# DynStudent.net
KiCad netlist of a schematic drawn in Altium Designer
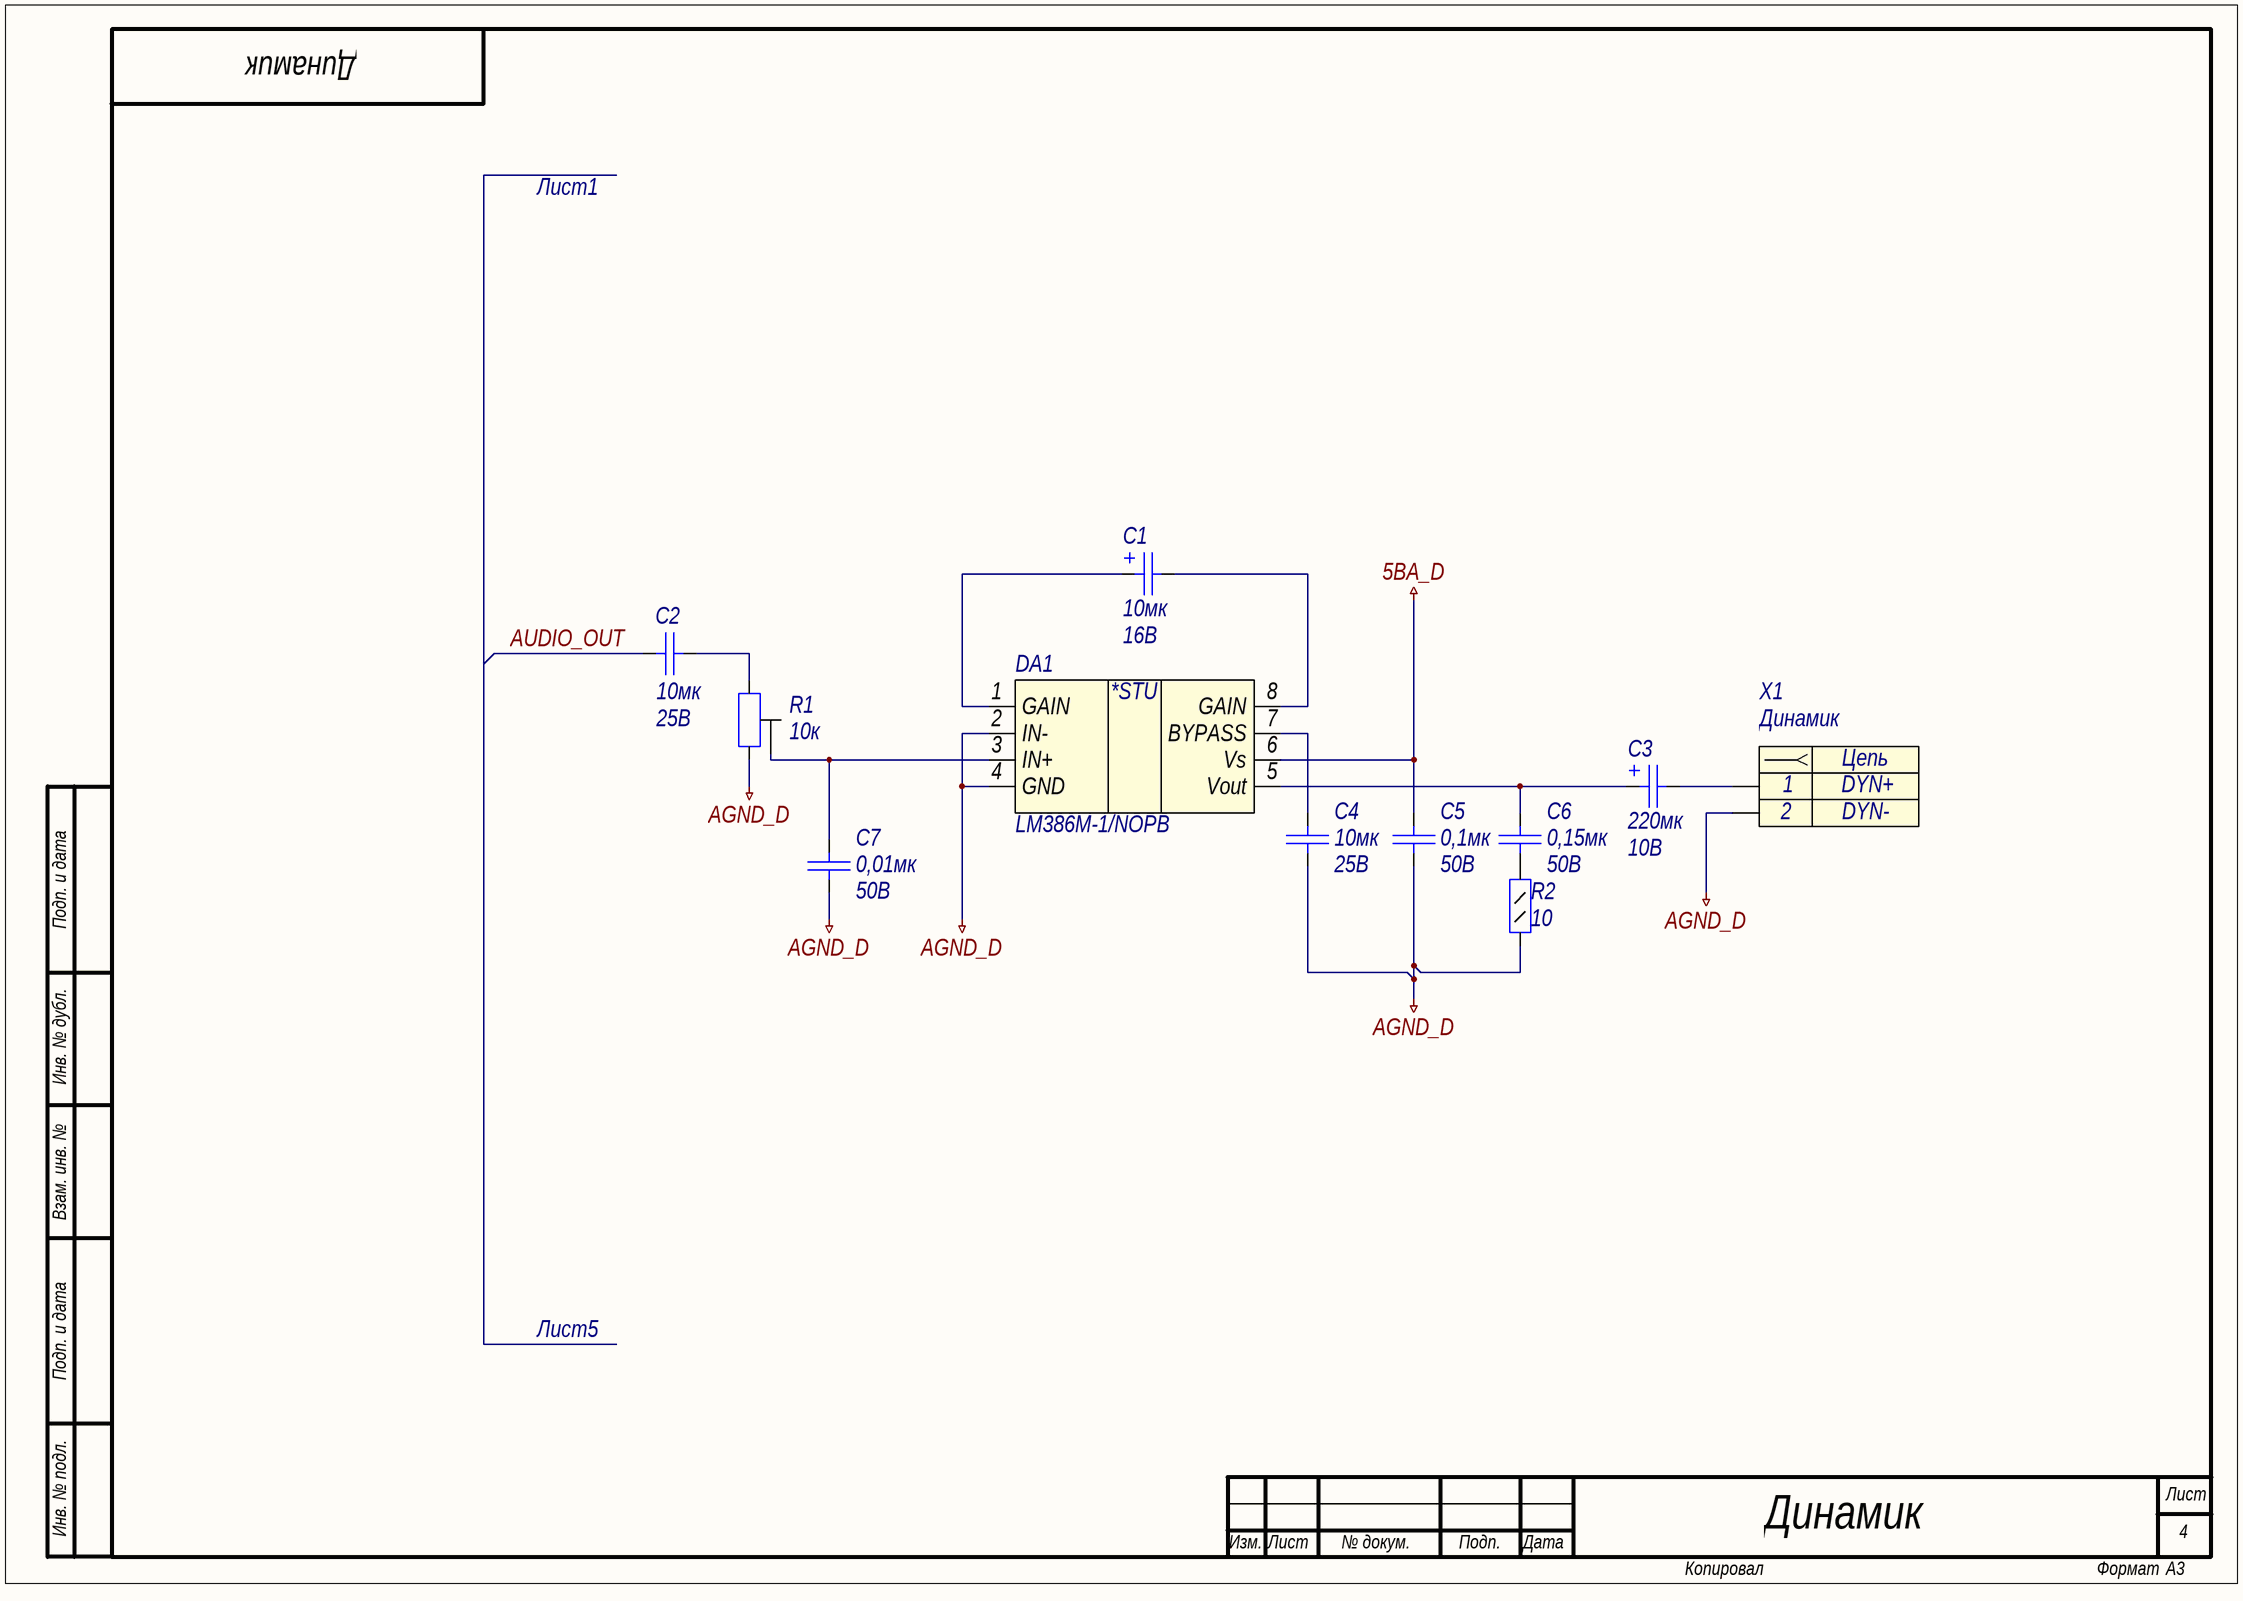
[diagram p0: DynStudent.SchDoc]

(export (version "E")
  (design (tool "Eeschema 10.0.6"))
  (components
    (comp (ref "C1")
      (value "10мк")
      (footprint "TANTAL CASE D")
      (description "Конденсатор полярный")
      (fields
        (field (name "VOLTAGE") "16В")
        (field (name "PART NUMBER") "ECASD41C106M060K")
        (field (name "Comment") "Capacitor_pol")
      )
      (libsource (lib "MOP44") (part "Capacitor_pol"))
    )
    (comp (ref "C2")
      (value "10мк")
      (footprint "C1210")
      (description "Конденсатор")
      (fields
        (field (name "VOLTAGE") "25В")
        (field (name "PART NUMBER") "GRM32ER61A106K")
        (field (name "Comment") "Capacitor")
      )
      (libsource (lib "MOP44") (part "Capacitor"))
    )
    (comp (ref "C3")
      (value "220мк")
      (footprint "TANTAL CASE D")
      (description "Конденсатор полярный")
      (fields
        (field (name "VOLTAGE") "10B")
        (field (name "PART NUMBER") "T491D227K016ZT")
        (field (name "Comment") "Capacitor_pol")
      )
      (libsource (lib "MOP44") (part "Capacitor_pol"))
    )
    (comp (ref "C4")
      (value "10мк")
      (footprint "C1206")
      (description "Конденсатор")
      (fields
        (field (name "VOLTAGE") "25В")
        (field (name "PART NUMBER") "GRM31CR71E106KA12L*")
        (field (name "Comment") "Capacitor")
      )
      (libsource (lib "MOP44") (part "Capacitor"))
    )
    (comp (ref "C5")
      (value "0,1мк")
      (footprint "C0805")
      (description "Конденсатор")
      (fields
        (field (name "VOLTAGE") "50B")
        (field (name "PART NUMBER") "GRM21BR71H104K**")
        (field (name "Comment") "Capacitor")
      )
      (libsource (lib "MOP44") (part "Capacitor"))
    )
    (comp (ref "C6")
      (value "0,15мк")
      (footprint "C0805")
      (description "Конденсатор")
      (fields
        (field (name "VOLTAGE") "50B")
        (field (name "PART NUMBER") "GRM21BR71H154K")
        (field (name "Comment") "Capacitor")
      )
      (libsource (lib "MOP44") (part "Capacitor"))
    )
    (comp (ref "C7")
      (value "0,01мк")
      (footprint "C0805")
      (description "Конденсатор")
      (fields
        (field (name "VOLTAGE") "50B")
        (field (name "PART NUMBER") "GRM216R71H103K")
        (field (name "Comment") "Capacitor")
      )
      (libsource (lib "MOP44") (part "Capacitor"))
    )
    (comp (ref "DA1")
      (value "LM386M-1/NOPB")
      (footprint "SO8")
      (description "Low Voltage Audio Power Amplifier")
      (libsource (lib "MOP44") (part "LM386M-1/NOPB"))
    )
    (comp (ref "R1")
      (value "10к")
      (footprint "Potentiometer")
      (description "Potentiometer")
      (fields (field (name "POWER") "0,15Вт") (field (name "PART NUMBER") "3302X-3-103"))
      (libsource (lib "MOP44") (part "Potentiometer"))
    )
    (comp (ref "R2")
      (value "10")
      (footprint "R0805")
      (description "Резистор")
      (fields (field (name "PART NUMBER") "RC0805FR-0710RL") (field (name "POWER") "0,125Вт"))
      (libsource (lib "MOP44") (part "Resistor_0,125Вт"))
    )
    (comp (ref "X1")
      (value "Динамик")
      (footprint "CWF-2R")
      (description "Разъем - 2 конт. розетка")
      (fields (field (name "PART NUMBER") "DS1069-2 MR-A"))
      (libsource (lib "MOP44") (part "Header_2_sct"))
    )
  )
  (nets
    (net (code "1") (name "/AUDIO_OUT") (class "Default")
      (node (ref "C2") (pin "1") (pinfunction "1_1") (pintype "passive"))
    )
    (net (code "2") (name "5BA_D") (class "Default")
      (node (ref "C5") (pin "2") (pinfunction "2_2") (pintype "passive"))
      (node (ref "DA1") (pin "6") (pinfunction "Vs_6") (pintype "power_in"))
    )
    (net (code "3") (name "AGND_D") (class "Default")
      (node (ref "C4") (pin "1") (pinfunction "1_1") (pintype "passive"))
      (node (ref "C5") (pin "1") (pinfunction "1_1") (pintype "passive"))
      (node (ref "C7") (pin "1") (pinfunction "1_1") (pintype "passive"))
      (node (ref "DA1") (pin "2") (pinfunction "IN-_2") (pintype "power_in"))
      (node (ref "DA1") (pin "4") (pinfunction "GND_4") (pintype "power_in"))
      (node (ref "R1") (pin "3") (pinfunction "3_3") (pintype "passive"))
      (node (ref "R2") (pin "1") (pinfunction "1_1") (pintype "passive"))
      (node (ref "X1") (pin "2") (pinfunction "2_2") (pintype "passive"))
    )
    (net (code "4") (name "Net-(C1-Pad1)") (class "Default")
      (node (ref "C1") (pin "1") (pinfunction "1_1") (pintype "passive"))
      (node (ref "DA1") (pin "1") (pinfunction "GAIN_1") (pintype "power_in"))
    )
    (net (code "5") (name "Net-(C1-Pad2)") (class "Default")
      (node (ref "C1") (pin "2") (pinfunction "2_2") (pintype "passive"))
      (node (ref "DA1") (pin "8") (pinfunction "GAIN_8") (pintype "power_in"))
    )
    (net (code "6") (name "Net-(C2-Pad2)") (class "Default")
      (node (ref "C2") (pin "2") (pinfunction "2_2") (pintype "passive"))
      (node (ref "R1") (pin "1") (pinfunction "1_1") (pintype "passive"))
    )
    (net (code "7") (name "Net-(C3-Pad2)") (class "Default")
      (node (ref "C3") (pin "2") (pinfunction "2_2") (pintype "passive"))
      (node (ref "X1") (pin "1") (pinfunction "1_1") (pintype "passive"))
    )
    (net (code "8") (name "Net-(C6-Pad1)") (class "Default")
      (node (ref "C6") (pin "1") (pinfunction "1_1") (pintype "passive"))
      (node (ref "R2") (pin "2") (pinfunction "2_2") (pintype "passive"))
    )
    (net (code "9") (name "Net-(DA1-BYPASS)") (class "Default")
      (node (ref "C4") (pin "2") (pinfunction "2_2") (pintype "passive"))
      (node (ref "DA1") (pin "7") (pinfunction "BYPASS_7") (pintype "power_in"))
    )
    (net (code "10") (name "Net-(DA1-IN+)") (class "Default")
      (node (ref "C7") (pin "2") (pinfunction "2_2") (pintype "passive"))
      (node (ref "DA1") (pin "3") (pinfunction "IN+_3") (pintype "power_in"))
      (node (ref "R1") (pin "2") (pinfunction "2_2") (pintype "passive"))
    )
    (net (code "11") (name "Net-(DA1-Vout)") (class "Default")
      (node (ref "C3") (pin "1") (pinfunction "1_1") (pintype "passive"))
      (node (ref "C6") (pin "2") (pinfunction "2_2") (pintype "passive"))
      (node (ref "DA1") (pin "5") (pinfunction "Vout_5") (pintype "power_in"))
    )
  )
)
